# Power.net
KiCad netlist of a schematic drawn in Altium Designer
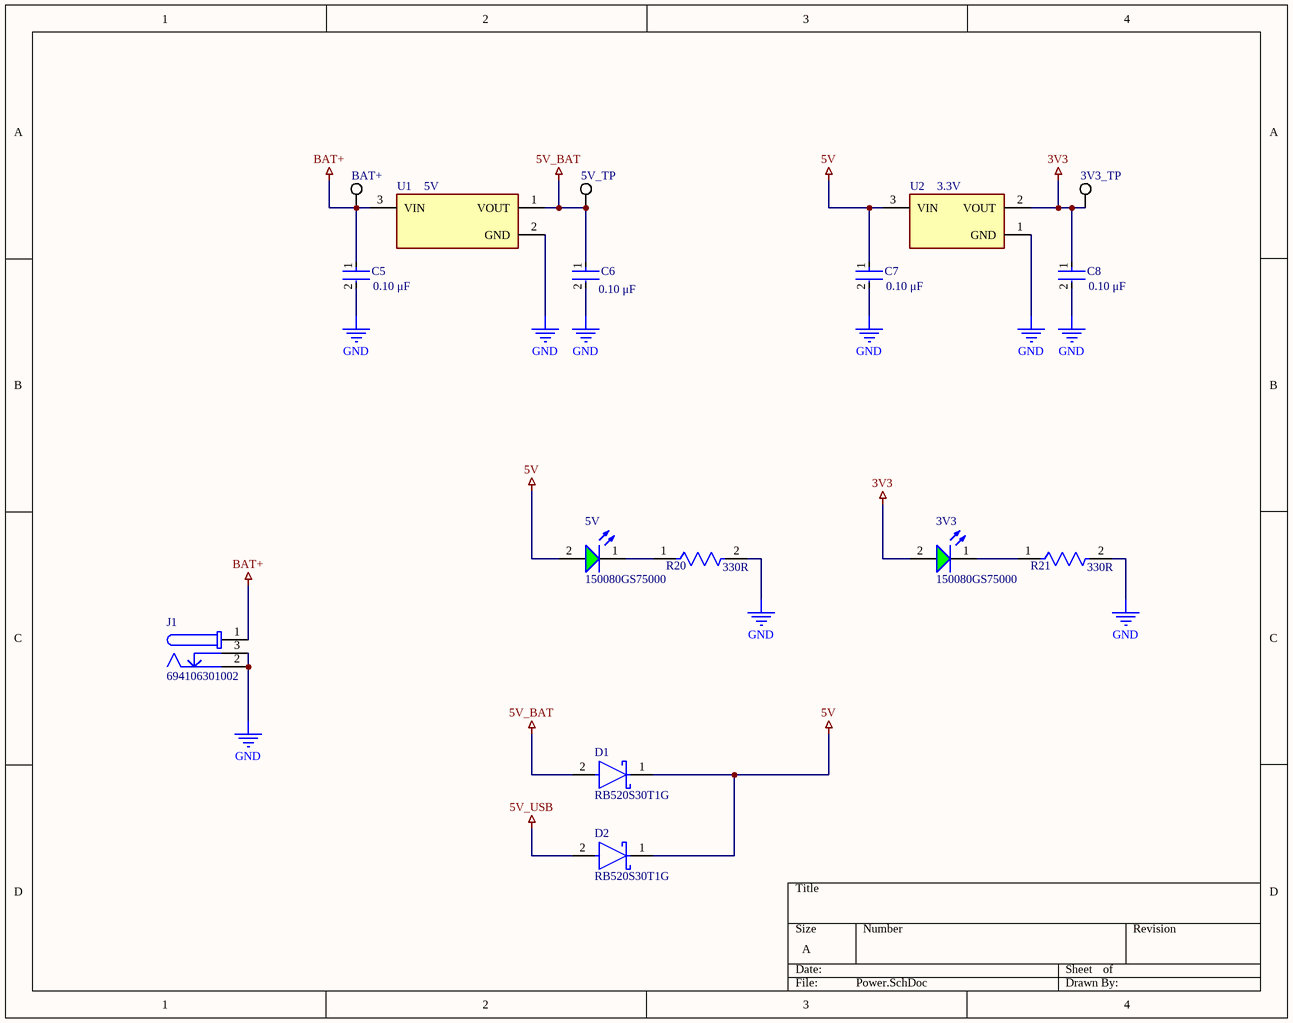
[diagram p0: Power.SchDoc]

(export (version "E")
  (design (tool "Eeschema 10.0.6"))
  (components
    (comp (ref "3V3")
      (value "150080GS75000")
      (footprint "WL-SMCW_0805_150080xx75000")
      (description "Single Color LED, Green, Water Clear, 1.4mm")
      (fields (field (name "MANUFACTURER") "Wurth Electronics"))
      (libsource (lib "Altium Content Vault") (part "LED_Green_2A-1K"))
    )
    (comp (ref "3V3_TP")
      (value "~")
      (footprint "KSTN-5019_V")
      (description "Test Point, 1 Position SMD, RoHS, Tape and Reel")
      (fields
        (field (name "MANUFACTURER") "Keystone Electronics")
        (field (name "MANUFACTURER PART NUMBER") "5019")
      )
      (libsource (lib "Altium Content Vault") (part "TESTPOINT_WHITE"))
    )
    (comp (ref "5V")
      (value "150080GS75000")
      (footprint "WL-SMCW_0805_150080xx75000")
      (description "Single Color LED, Green, Water Clear, 1.4mm")
      (fields (field (name "MANUFACTURER") "Wurth Electronics"))
      (libsource (lib "Altium Content Vault") (part "LED_Green_2A-1K"))
    )
    (comp (ref "5V_TP")
      (value "~")
      (footprint "KSTN-5019_V")
      (description "Test Point, 1 Position SMD, RoHS, Tape and Reel")
      (fields
        (field (name "MANUFACTURER") "Keystone Electronics")
        (field (name "MANUFACTURER PART NUMBER") "5019")
      )
      (libsource (lib "Altium Content Vault") (part "TESTPOINT_WHITE"))
    )
    (comp (ref "BAT+")
      (value "~")
      (footprint "KSTN-5019_V")
      (description "Test Point, 1 Position SMD, RoHS, Tape and Reel")
      (fields
        (field (name "MANUFACTURER") "Keystone Electronics")
        (field (name "MANUFACTURER PART NUMBER") "5019")
      )
      (libsource (lib "Altium Content Vault") (part "TESTPOINT_WHITE"))
    )
    (comp (ref "C5")
      (value "C0603C104K5RACTU")
      (footprint "FP-C0603C-CF-MFG")
      (description "CAP CER 0.1UF 50V X7R 0603")
      (fields
        (field (name "TOLERANCE") "0.1")
        (field (name "MANUFACTURER") "KEMET")
        (field (name "CAPACITANCE") "0.10 μF")
      )
      (libsource (lib "Altium Content Vault") (part "b4654b650e69147ec39a6b967a45e02"))
    )
    (comp (ref "C6")
      (value "C0603C104K5RACTU")
      (footprint "FP-C0603C-CF-MFG")
      (description "CAP CER 0.1UF 50V X7R 0603")
      (fields
        (field (name "TOLERANCE") "0.1")
        (field (name "MANUFACTURER") "KEMET")
        (field (name "CAPACITANCE") "0.10 μF")
      )
      (libsource (lib "Altium Content Vault") (part "b4654b650e69147ec39a6b967a45e02"))
    )
    (comp (ref "C7")
      (value "C0603C104K5RACTU")
      (footprint "FP-C0603C-CF-MFG")
      (description "CAP CER 0.1UF 50V X7R 0603")
      (fields
        (field (name "TOLERANCE") "0.1")
        (field (name "MANUFACTURER") "KEMET")
        (field (name "CAPACITANCE") "0.10 μF")
      )
      (libsource (lib "Altium Content Vault") (part "b4654b650e69147ec39a6b967a45e02"))
    )
    (comp (ref "C8")
      (value "C0603C104K5RACTU")
      (footprint "FP-C0603C-CF-MFG")
      (description "CAP CER 0.1UF 50V X7R 0603")
      (fields
        (field (name "TOLERANCE") "0.1")
        (field (name "MANUFACTURER") "KEMET")
        (field (name "CAPACITANCE") "0.10 μF")
      )
      (libsource (lib "Altium Content Vault") (part "b4654b650e69147ec39a6b967a45e02"))
    )
    (comp (ref "D1")
      (value "RB520S30T1G")
      (footprint "FP-502-01-MFG")
      (description "DIODE SCHOTTKY 30V 200MA SOD523")
      (libsource (lib "Altium Content Vault") (part "1d6ec82d83fb6aee721767c19dac4b9"))
    )
    (comp (ref "D2")
      (value "RB520S30T1G")
      (footprint "FP-502-01-MFG")
      (description "DIODE SCHOTTKY 30V 200MA SOD523")
      (libsource (lib "Altium Content Vault") (part "1d6ec82d83fb6aee721767c19dac4b9"))
    )
    (comp (ref "J1")
      (value "694106301002")
      (footprint "694106301002")
      (fields (field (name "MANUFACTURER") "Wurth Electronics"))
      (libsource (lib "Altium Content Vault") (part "DC Power Jack"))
    )
    (comp (ref "R20")
      (value "CRCW0805330RFKEA")
      (footprint "FP-CRCW0805-e3-MFG")
      (description "RES Thick Film, 330Ω, 1%, 0.125W, 100ppm/°C, 0805")
      (fields
        (field (name "RESISTANCE") "330R")
        (field (name "TOLERANCE") "1%")
        (field (name "MANUFACTURER") "Vishay")
      )
      (libsource (lib "Altium Content Vault") (part "1029c3af85768c4190bb7ad29bc67b5"))
    )
    (comp (ref "R21")
      (value "CRCW0805330RFKEA")
      (footprint "FP-CRCW0805-e3-MFG")
      (description "RES Thick Film, 330Ω, 1%, 0.125W, 100ppm/°C, 0805")
      (fields
        (field (name "RESISTANCE") "330R")
        (field (name "TOLERANCE") "1%")
        (field (name "MANUFACTURER") "Vishay")
      )
      (libsource (lib "Altium Content Vault") (part "1029c3af85768c4190bb7ad29bc67b5"))
    )
    (comp (ref "U1")
      (value "L78L05ACUTR")
      (footprint "FP-SOT-89-7098166-MFG")
      (description "IC REG LINEAR 5V 100MA SOT89-3")
      (fields (field (name "OUTPUT VOLTAGE") "5V") (field (name "MANUFACTURER") "STMicroelectronics"))
      (libsource (lib "Altium Content Vault") (part "ae6bee9076d4e2dbe8e374331bf90c1"))
    )
    (comp (ref "U2")
      (value "AP2120N-3.3TRG1")
      (footprint "FP-SOT23-MFG")
      (description "IC REG LINEAR 3.3V 150MA SOT23")
      (fields
        (field (name "OUTPUT VOLTAGE") "3.3V")
        (field (name "MANUFACTURER") "Diodes Inc.")
        (field (name "OCTOPART") "https://octopart.com/ap2120n-3.3trg1-diodes+inc.-30954573")
      )
      (libsource (lib "Altium Content Vault") (part "340b21d0b7389e2ba8b62ca99e39354"))
    )
  )
  (nets
    (net (code "1") (name "3V3") (class "Default")
      (node (ref "3V3") (pin "2") (pinfunction "A_2") (pintype "passive"))
      (node (ref "3V3_TP") (pin "1") (pinfunction "1_1") (pintype "passive"))
      (node (ref "C8") (pin "1") (pinfunction "1_1") (pintype "passive"))
      (node (ref "U2") (pin "2") (pinfunction "VOUT_2") (pintype "power_in"))
    )
    (net (code "2") (name "5V") (class "Default")
      (node (ref "5V") (pin "2") (pinfunction "A_2") (pintype "passive"))
      (node (ref "C7") (pin "1") (pinfunction "1_1") (pintype "passive"))
      (node (ref "D1") (pin "1") (pinfunction "C_1") (pintype "passive"))
      (node (ref "D2") (pin "1") (pinfunction "C_1") (pintype "passive"))
      (node (ref "U2") (pin "3") (pinfunction "VIN_3") (pintype "power_in"))
    )
    (net (code "3") (name "5V_BAT") (class "Default")
      (node (ref "5V_TP") (pin "1") (pinfunction "1_1") (pintype "passive"))
      (node (ref "C6") (pin "1") (pinfunction "1_1") (pintype "passive"))
      (node (ref "D1") (pin "2") (pinfunction "A_2") (pintype "passive"))
      (node (ref "U1") (pin "1") (pinfunction "VOUT_1") (pintype "power_in"))
    )
    (net (code "4") (name "5V_USB") (class "Default")
      (node (ref "D2") (pin "2") (pinfunction "A_2") (pintype "passive"))
    )
    (net (code "5") (name "BAT+") (class "Default")
      (node (ref "BAT+") (pin "1") (pinfunction "1_1") (pintype "passive"))
      (node (ref "C5") (pin "1") (pinfunction "1_1") (pintype "passive"))
      (node (ref "J1") (pin "1") (pinfunction "1_1") (pintype "passive"))
      (node (ref "U1") (pin "3") (pinfunction "VIN_3") (pintype "power_in"))
    )
    (net (code "6") (name "GND") (class "Default")
      (node (ref "C5") (pin "2") (pinfunction "2_2") (pintype "passive"))
      (node (ref "C6") (pin "2") (pinfunction "2_2") (pintype "passive"))
      (node (ref "C7") (pin "2") (pinfunction "2_2") (pintype "passive"))
      (node (ref "C8") (pin "2") (pinfunction "2_2") (pintype "passive"))
      (node (ref "J1") (pin "2") (pinfunction "2_2") (pintype "passive"))
      (node (ref "J1") (pin "3") (pinfunction "3_3") (pintype "passive"))
      (node (ref "R20") (pin "2") (pinfunction "2_2") (pintype "passive"))
      (node (ref "R21") (pin "2") (pinfunction "2_2") (pintype "passive"))
      (node (ref "U1") (pin "2") (pinfunction "GND_2") (pintype "power_in"))
      (node (ref "U2") (pin "1") (pinfunction "GND_1") (pintype "power_in"))
    )
    (net (code "7") (name "Net-(3V3-K)") (class "Default")
      (node (ref "3V3") (pin "1") (pinfunction "K_1") (pintype "passive"))
      (node (ref "R21") (pin "1") (pinfunction "1_1") (pintype "passive"))
    )
    (net (code "8") (name "Net-(5V-K)") (class "Default")
      (node (ref "5V") (pin "1") (pinfunction "K_1") (pintype "passive"))
      (node (ref "R20") (pin "1") (pinfunction "1_1") (pintype "passive"))
    )
  )
)
